# HVIBDC.net
KiCad netlist of a schematic drawn in EAGLE
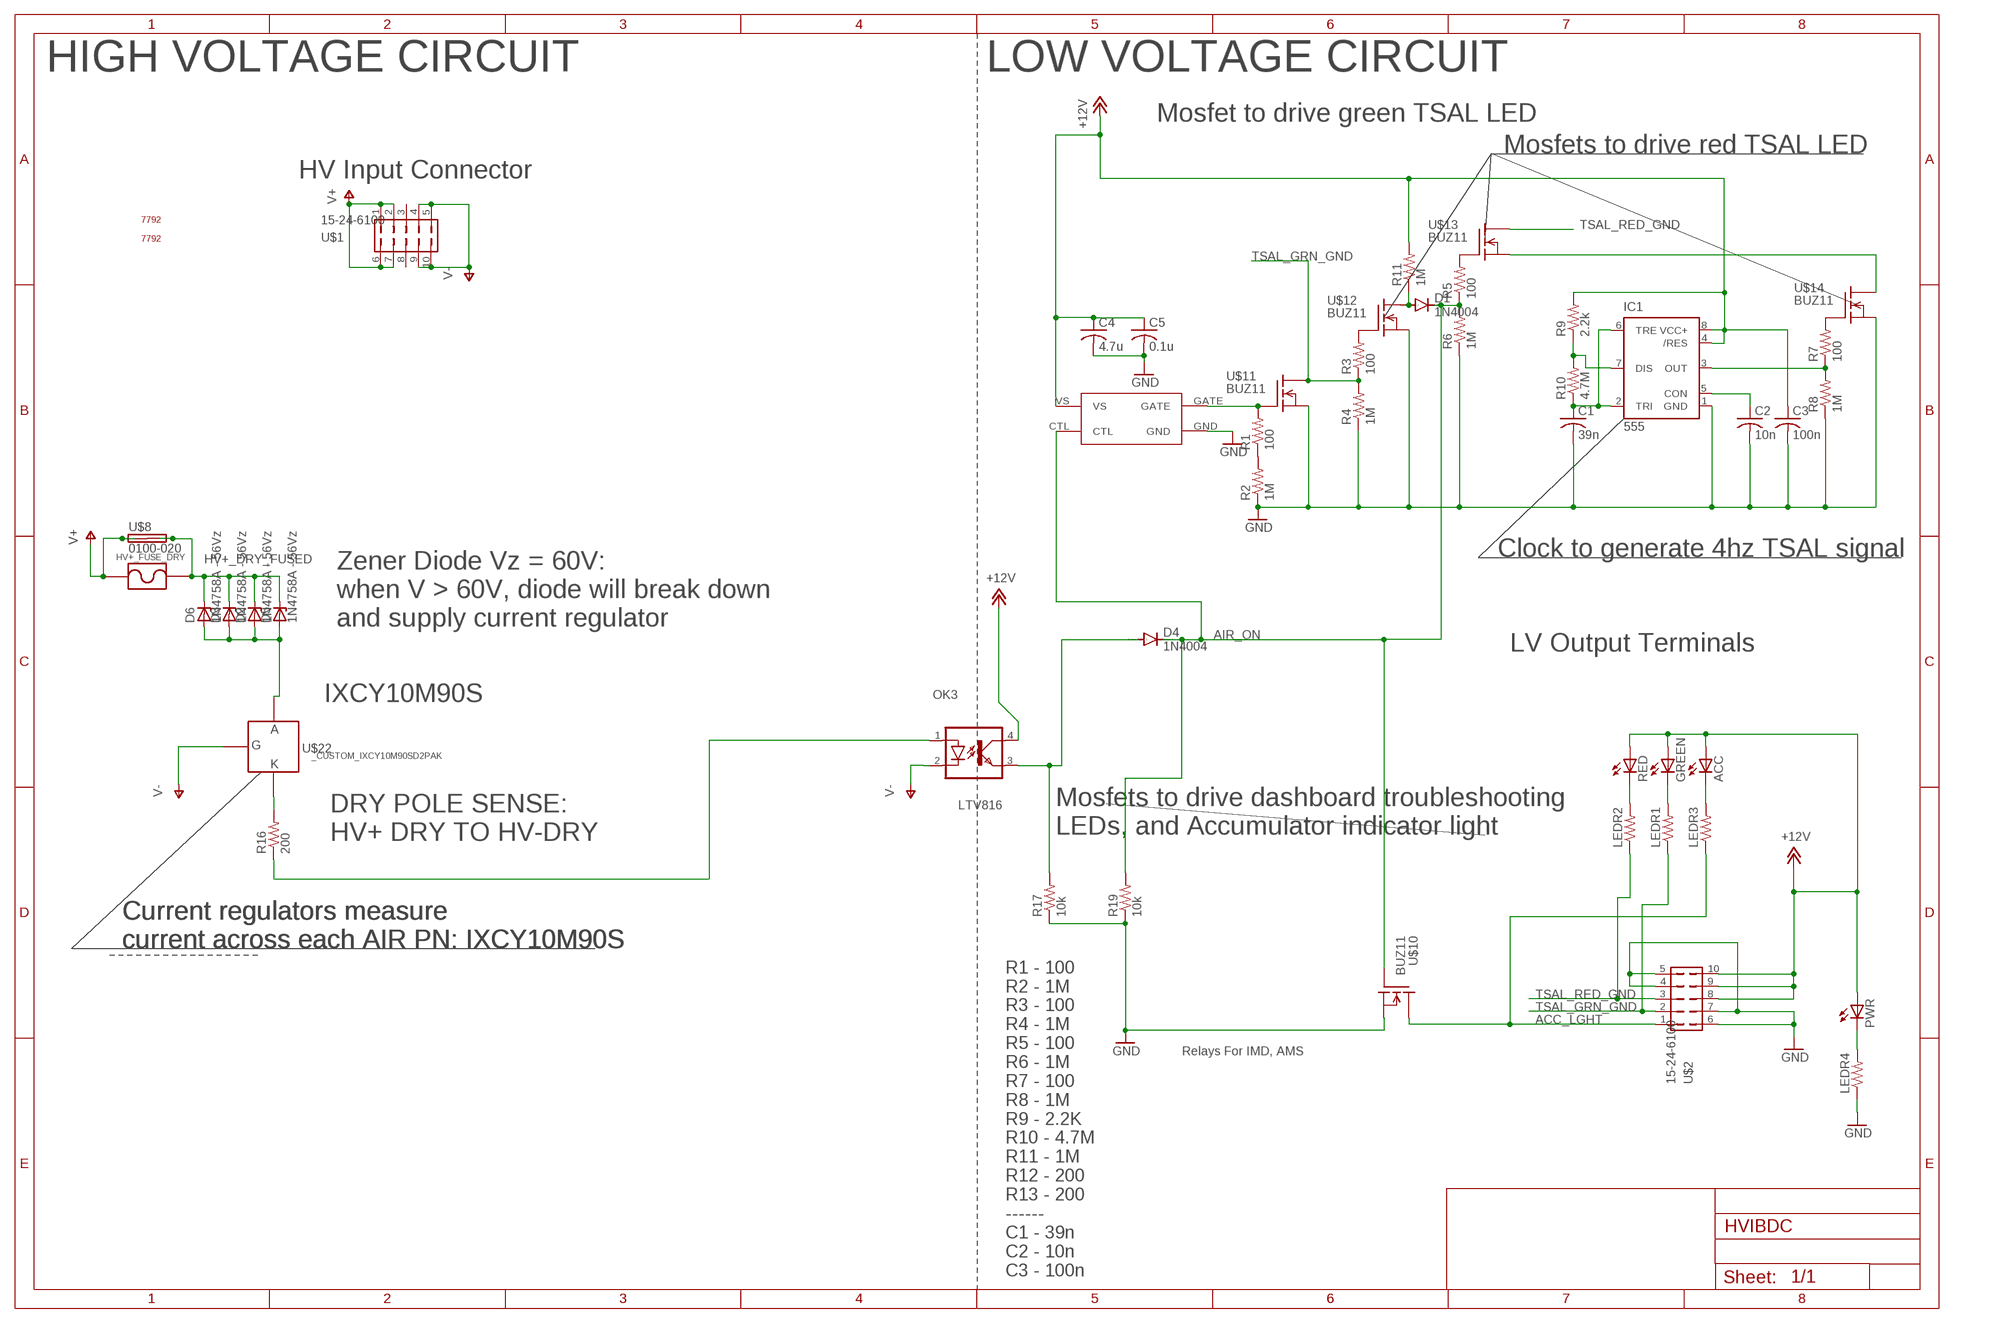
[diagram p0: schematic, sheet 1]

(export (version "E")
  (design (tool "Eeschema 10.0.6"))
  (components
    (comp (ref "ACC")
      (value "LEDCHIPLED_0805")
      (footprint "eagle-import:CHIPLED_0805")
      (libsource (lib "eagle-import") (part "LEDCHIPLED_0805"))
    )
    (comp (ref "C1")
      (value "39n")
      (footprint "eagle-import:C0805")
      (libsource (lib "eagle-import") (part "C-USC0805"))
    )
    (comp (ref "C2")
      (value "10n")
      (footprint "eagle-import:C0805")
      (libsource (lib "eagle-import") (part "C-USC0805"))
    )
    (comp (ref "C3")
      (value "100n")
      (footprint "eagle-import:C0805")
      (libsource (lib "eagle-import") (part "C-USC0805"))
    )
    (comp (ref "C4")
      (value "4.7u")
      (footprint "eagle-import:C0805")
      (libsource (lib "eagle-import") (part "C-USC0805"))
    )
    (comp (ref "C5")
      (value "0.1u")
      (footprint "eagle-import:C0805")
      (libsource (lib "eagle-import") (part "C-USC0805"))
    )
    (comp (ref "D1")
      (value "1N4004")
      (footprint "eagle-import:DO41-10")
      (libsource (lib "eagle-import") (part "1N4004"))
    )
    (comp (ref "D2")
      (value "1N4758A - 56Vz")
      (footprint "eagle-import:ZDIO12.5")
      (libsource (lib "eagle-import") (part "ZENER-DIODEZD-12.5"))
    )
    (comp (ref "D3")
      (value "1N4758A - 56Vz")
      (footprint "eagle-import:ZDIO12.5")
      (libsource (lib "eagle-import") (part "ZENER-DIODEZD-12.5"))
    )
    (comp (ref "D4")
      (value "1N4004")
      (footprint "eagle-import:DO41-10")
      (libsource (lib "eagle-import") (part "1N4004"))
    )
    (comp (ref "D5")
      (value "1N4758A - 56Vz")
      (footprint "eagle-import:ZDIO12.5")
      (libsource (lib "eagle-import") (part "ZENER-DIODEZD-12.5"))
    )
    (comp (ref "D6")
      (value "1N4758A - 56Vz")
      (footprint "eagle-import:ZDIO12.5")
      (libsource (lib "eagle-import") (part "ZENER-DIODEZD-12.5"))
    )
    (comp (ref "GREEN")
      (value "LEDCHIPLED_0805")
      (footprint "eagle-import:CHIPLED_0805")
      (libsource (lib "eagle-import") (part "LEDCHIPLED_0805"))
    )
    (comp (ref "HV+_FUSE_DRY")
      (value "_CUSTOM_PARTS_LF_885")
      (footprint "eagle-import:_CUSTOM_PARTS_LF_885")
      (libsource (lib "eagle-import") (part "_CUSTOM_PARTS_LF_885"))
    )
    (comp (ref "IC1")
      (value "555")
      (footprint "eagle-import:DIP08")
      (libsource (lib "eagle-import") (part "555P"))
    )
    (comp (ref "LEDR1")
      (value "R-US_R0805")
      (footprint "eagle-import:R0805")
      (libsource (lib "eagle-import") (part "R-US_R0805"))
    )
    (comp (ref "LEDR2")
      (value "R-US_R0805")
      (footprint "eagle-import:R0805")
      (libsource (lib "eagle-import") (part "R-US_R0805"))
    )
    (comp (ref "LEDR3")
      (value "R-US_R0805")
      (footprint "eagle-import:R0805")
      (libsource (lib "eagle-import") (part "R-US_R0805"))
    )
    (comp (ref "LEDR4")
      (value "R-US_R0805")
      (footprint "eagle-import:R0805")
      (libsource (lib "eagle-import") (part "R-US_R0805"))
    )
    (comp (ref "OK3")
      (value "LTV816")
      (footprint "eagle-import:DIL04")
      (libsource (lib "eagle-import") (part "LTV816"))
    )
    (comp (ref "PWR")
      (value "LEDCHIPLED_0805")
      (footprint "eagle-import:CHIPLED_0805")
      (libsource (lib "eagle-import") (part "LEDCHIPLED_0805"))
    )
    (comp (ref "R1")
      (value "100")
      (footprint "eagle-import:R0805")
      (libsource (lib "eagle-import") (part "resistor_348_R-US_R0805"))
    )
    (comp (ref "R2")
      (value "1M")
      (footprint "eagle-import:R0805")
      (libsource (lib "eagle-import") (part "resistor_348_R-US_R0805"))
    )
    (comp (ref "R3")
      (value "100")
      (footprint "eagle-import:R0805")
      (libsource (lib "eagle-import") (part "resistor_348_R-US_R0805"))
    )
    (comp (ref "R4")
      (value "1M")
      (footprint "eagle-import:R0805")
      (libsource (lib "eagle-import") (part "resistor_348_R-US_R0805"))
    )
    (comp (ref "R5")
      (value "100")
      (footprint "eagle-import:R0805")
      (libsource (lib "eagle-import") (part "resistor_348_R-US_R0805"))
    )
    (comp (ref "R6")
      (value "1M")
      (footprint "eagle-import:R0805")
      (libsource (lib "eagle-import") (part "resistor_348_R-US_R0805"))
    )
    (comp (ref "R7")
      (value "100")
      (footprint "eagle-import:R0805")
      (libsource (lib "eagle-import") (part "resistor_348_R-US_R0805"))
    )
    (comp (ref "R8")
      (value "1M")
      (footprint "eagle-import:R0805")
      (libsource (lib "eagle-import") (part "resistor_348_R-US_R0805"))
    )
    (comp (ref "R9")
      (value "2.2k")
      (footprint "eagle-import:R0805")
      (libsource (lib "eagle-import") (part "resistor_348_R-US_R0805"))
    )
    (comp (ref "R10")
      (value "4.7M")
      (footprint "eagle-import:R0805")
      (libsource (lib "eagle-import") (part "resistor_348_R-US_R0805"))
    )
    (comp (ref "R11")
      (value "1M")
      (footprint "eagle-import:R0805")
      (libsource (lib "eagle-import") (part "resistor_348_R-US_R0805"))
    )
    (comp (ref "R16")
      (value "200")
      (footprint "eagle-import:R2010")
      (libsource (lib "eagle-import") (part "Main_14107900_R-US_R2010"))
    )
    (comp (ref "R17")
      (value "10k")
      (footprint "eagle-import:R0805")
      (libsource (lib "eagle-import") (part "resistor_348_R-US_R0805"))
    )
    (comp (ref "R19")
      (value "10k")
      (footprint "eagle-import:R0805")
      (libsource (lib "eagle-import") (part "resistor_348_R-US_R0805"))
    )
    (comp (ref "RED")
      (value "LEDCHIPLED_0805")
      (footprint "eagle-import:CHIPLED_0805")
      (libsource (lib "eagle-import") (part "LEDCHIPLED_0805"))
    )
    (comp (ref "U$1")
      (value "15-24-6100")
      (footprint "eagle-import:15-24-6100")
      (libsource (lib "eagle-import") (part "15-24-6100"))
    )
    (comp (ref "U$2")
      (value "15-24-6100")
      (footprint "eagle-import:15-24-6100")
      (libsource (lib "eagle-import") (part "15-24-6100"))
    )
    (comp (ref "U$3")
      (value "7792")
      (footprint "eagle-import:7792")
      (libsource (lib "eagle-import") (part "7792"))
    )
    (comp (ref "U$4")
      (value "7792")
      (footprint "eagle-import:7792")
      (libsource (lib "eagle-import") (part "7792"))
    )
    (comp (ref "U$8")
      (value "0100-020")
      (footprint "eagle-import:0100-020")
      (libsource (lib "eagle-import") (part "0100-020"))
    )
    (comp (ref "U$10")
      (value "BUZ11")
      (footprint "eagle-import:TO220")
      (libsource (lib "eagle-import") (part "BUZ11"))
    )
    (comp (ref "U$11")
      (value "BUZ11")
      (footprint "eagle-import:TO220")
      (libsource (lib "eagle-import") (part "BUZ11"))
    )
    (comp (ref "U$12")
      (value "BUZ11")
      (footprint "eagle-import:TO220")
      (libsource (lib "eagle-import") (part "BUZ11"))
    )
    (comp (ref "U$13")
      (value "BUZ11")
      (footprint "eagle-import:TO220")
      (libsource (lib "eagle-import") (part "BUZ11"))
    )
    (comp (ref "U$14")
      (value "BUZ11")
      (footprint "eagle-import:TO220")
      (libsource (lib "eagle-import") (part "BUZ11"))
    )
    (comp (ref "U$15")
      (value "MIC4417")
      (footprint "eagle-import:PDM_2019_REVB_MIC4416YM4-TR")
      (libsource (lib "eagle-import") (part "MIC4417"))
    )
    (comp (ref "U$22")
      (value "_CUSTOM_IXCY10M90SD2PAK")
      (footprint "eagle-import:TO228P991X238-3")
      (libsource (lib "eagle-import") (part "_CUSTOM_IXCY10M90SD2PAK"))
    )
  )
  (nets
    (net (code "1") (name "+12V") (class "Default")
      (node (ref "ACC") (pin "A") (pinfunction "A_A") (pintype "passive"))
      (node (ref "C3") (pin "1") (pinfunction "1_1") (pintype "passive"))
      (node (ref "C4") (pin "1") (pinfunction "1_1") (pintype "passive"))
      (node (ref "C5") (pin "1") (pinfunction "1_1") (pintype "passive"))
      (node (ref "GREEN") (pin "A") (pinfunction "A_A") (pintype "passive"))
      (node (ref "IC1") (pin "4") (pinfunction "/RES_4") (pintype "input"))
      (node (ref "IC1") (pin "8") (pinfunction "VCC+_8") (pintype "power_in"))
      (node (ref "OK3") (pin "4") (pinfunction "COL_4") (pintype "passive"))
      (node (ref "PWR") (pin "A") (pinfunction "A_A") (pintype "passive"))
      (node (ref "R11") (pin "2") (pinfunction "2_2") (pintype "passive"))
      (node (ref "R9") (pin "2") (pinfunction "2_2") (pintype "passive"))
      (node (ref "RED") (pin "A") (pinfunction "A_A") (pintype "passive"))
      (node (ref "U$15") (pin "VS") (pinfunction "VS_VS") (pintype "bidirectional"))
      (node (ref "U$2") (pin "10") (pinfunction "10_10") (pintype "passive"))
      (node (ref "U$2") (pin "8") (pinfunction "8_8") (pintype "passive"))
      (node (ref "U$2") (pin "9") (pinfunction "9_9") (pintype "passive"))
    )
    (net (code "2") (name "/ACC_LGHT") (class "Default")
      (node (ref "LEDR3") (pin "1") (pinfunction "1_1") (pintype "passive"))
      (node (ref "U$10") (pin "2") (pinfunction "D_2") (pintype "passive"))
      (node (ref "U$2") (pin "1") (pinfunction "1_1") (pintype "passive"))
    )
    (net (code "3") (name "/AIR_ON") (class "Default")
      (node (ref "D1") (pin "C") (pinfunction "C_C") (pintype "passive"))
      (node (ref "D4") (pin "C") (pinfunction "C_C") (pintype "passive"))
      (node (ref "R19") (pin "2") (pinfunction "2_2") (pintype "passive"))
      (node (ref "R5") (pin "1") (pinfunction "1_1") (pintype "passive"))
      (node (ref "R6") (pin "2") (pinfunction "2_2") (pintype "passive"))
      (node (ref "U$10") (pin "1") (pinfunction "G_1") (pintype "passive"))
      (node (ref "U$15") (pin "CTL") (pinfunction "CTL_CTL") (pintype "bidirectional"))
    )
    (net (code "4") (name "/HV+_DRY_FUSED") (class "Default")
      (node (ref "D2") (pin "C") (pinfunction "C_C") (pintype "passive"))
      (node (ref "D3") (pin "C") (pinfunction "C_C") (pintype "passive"))
      (node (ref "D5") (pin "C") (pinfunction "C_C") (pintype "passive"))
      (node (ref "D6") (pin "C") (pinfunction "C_C") (pintype "passive"))
      (node (ref "HV+_FUSE_DRY") (pin "P$1") (pinfunction "P$1_P$1") (pintype "bidirectional"))
      (node (ref "U$8") (pin "P$2") (pinfunction "2A_P$2") (pintype "passive"))
      (node (ref "U$8") (pin "P$4") (pinfunction "2B_P$4") (pintype "passive"))
    )
    (net (code "5") (name "/TSAL_GRN_GND") (class "Default")
      (node (ref "LEDR1") (pin "1") (pinfunction "1_1") (pintype "passive"))
      (node (ref "R3") (pin "1") (pinfunction "1_1") (pintype "passive"))
      (node (ref "R4") (pin "2") (pinfunction "2_2") (pintype "passive"))
      (node (ref "U$11") (pin "2") (pinfunction "D_2") (pintype "passive"))
      (node (ref "U$2") (pin "2") (pinfunction "2_2") (pintype "passive"))
    )
    (net (code "6") (name "/TSAL_RED_GND") (class "Default")
      (node (ref "LEDR2") (pin "1") (pinfunction "1_1") (pintype "passive"))
      (node (ref "U$13") (pin "2") (pinfunction "D_2") (pintype "passive"))
      (node (ref "U$2") (pin "3") (pinfunction "3_3") (pintype "passive"))
    )
    (net (code "7") (name "GND") (class "Default")
      (node (ref "C1") (pin "2") (pinfunction "2_2") (pintype "passive"))
      (node (ref "C2") (pin "2") (pinfunction "2_2") (pintype "passive"))
      (node (ref "C3") (pin "2") (pinfunction "2_2") (pintype "passive"))
      (node (ref "C4") (pin "2") (pinfunction "2_2") (pintype "passive"))
      (node (ref "C5") (pin "2") (pinfunction "2_2") (pintype "passive"))
      (node (ref "IC1") (pin "1") (pinfunction "GND_1") (pintype "power_in"))
      (node (ref "LEDR4") (pin "1") (pinfunction "1_1") (pintype "passive"))
      (node (ref "R17") (pin "1") (pinfunction "1_1") (pintype "passive"))
      (node (ref "R19") (pin "1") (pinfunction "1_1") (pintype "passive"))
      (node (ref "R2") (pin "1") (pinfunction "1_1") (pintype "passive"))
      (node (ref "R4") (pin "1") (pinfunction "1_1") (pintype "passive"))
      (node (ref "R6") (pin "1") (pinfunction "1_1") (pintype "passive"))
      (node (ref "R8") (pin "1") (pinfunction "1_1") (pintype "passive"))
      (node (ref "U$10") (pin "3") (pinfunction "S_3") (pintype "passive"))
      (node (ref "U$11") (pin "3") (pinfunction "S_3") (pintype "passive"))
      (node (ref "U$12") (pin "3") (pinfunction "S_3") (pintype "passive"))
      (node (ref "U$14") (pin "3") (pinfunction "S_3") (pintype "passive"))
      (node (ref "U$15") (pin "GND") (pinfunction "GND_GND") (pintype "bidirectional"))
      (node (ref "U$2") (pin "4") (pinfunction "4_4") (pintype "passive"))
      (node (ref "U$2") (pin "5") (pinfunction "5_5") (pintype "passive"))
      (node (ref "U$2") (pin "6") (pinfunction "6_6") (pintype "passive"))
      (node (ref "U$2") (pin "7") (pinfunction "7_7") (pintype "passive"))
    )
    (net (code "8") (name "Net-(ACC-PadC)") (class "Default")
      (node (ref "ACC") (pin "C") (pinfunction "C_C") (pintype "passive"))
      (node (ref "LEDR3") (pin "2") (pinfunction "2_2") (pintype "passive"))
    )
    (net (code "9") (name "Net-(GREEN-PadC)") (class "Default")
      (node (ref "GREEN") (pin "C") (pinfunction "C_C") (pintype "passive"))
      (node (ref "LEDR1") (pin "2") (pinfunction "2_2") (pintype "passive"))
    )
    (net (code "10") (name "Net-(IC1-CON)") (class "Default")
      (node (ref "C2") (pin "1") (pinfunction "1_1") (pintype "passive"))
      (node (ref "IC1") (pin "5") (pinfunction "CON_5") (pintype "input"))
    )
    (net (code "11") (name "Net-(IC1-DIS)") (class "Default")
      (node (ref "IC1") (pin "7") (pinfunction "DIS_7") (pintype "input"))
      (node (ref "R10") (pin "2") (pinfunction "2_2") (pintype "passive"))
      (node (ref "R9") (pin "1") (pinfunction "1_1") (pintype "passive"))
    )
    (net (code "12") (name "Net-(IC1-OUT)") (class "Default")
      (node (ref "IC1") (pin "3") (pinfunction "OUT_3") (pintype "output"))
      (node (ref "R7") (pin "1") (pinfunction "1_1") (pintype "passive"))
      (node (ref "R8") (pin "2") (pinfunction "2_2") (pintype "passive"))
    )
    (net (code "13") (name "Net-(IC1-TRE)") (class "Default")
      (node (ref "C1") (pin "1") (pinfunction "1_1") (pintype "passive"))
      (node (ref "IC1") (pin "2") (pinfunction "TRI_2") (pintype "input"))
      (node (ref "IC1") (pin "6") (pinfunction "TRE_6") (pintype "input"))
      (node (ref "R10") (pin "1") (pinfunction "1_1") (pintype "passive"))
    )
    (net (code "14") (name "Net-(LEDR2-Pad2)") (class "Default")
      (node (ref "LEDR2") (pin "2") (pinfunction "2_2") (pintype "passive"))
      (node (ref "RED") (pin "C") (pinfunction "C_C") (pintype "passive"))
    )
    (net (code "15") (name "Net-(LEDR4-Pad2)") (class "Default")
      (node (ref "LEDR4") (pin "2") (pinfunction "2_2") (pintype "passive"))
      (node (ref "PWR") (pin "C") (pinfunction "C_C") (pintype "passive"))
    )
    (net (code "16") (name "Net-(OK3-A)") (class "Default")
      (node (ref "OK3") (pin "1") (pinfunction "A_1") (pintype "passive"))
      (node (ref "R16") (pin "1") (pinfunction "1_1") (pintype "passive"))
    )
    (net (code "17") (name "Net-(OK3-EMIT)") (class "Default")
      (node (ref "D4") (pin "A") (pinfunction "A_A") (pintype "passive"))
      (node (ref "OK3") (pin "3") (pinfunction "EMIT_3") (pintype "passive"))
      (node (ref "R17") (pin "2") (pinfunction "2_2") (pintype "passive"))
    )
    (net (code "18") (name "Net-(R1-Pad1)") (class "Default")
      (node (ref "R1") (pin "1") (pinfunction "1_1") (pintype "passive"))
      (node (ref "R2") (pin "2") (pinfunction "2_2") (pintype "passive"))
    )
    (net (code "19") (name "Net-(U$11-G)") (class "Default")
      (node (ref "R1") (pin "2") (pinfunction "2_2") (pintype "passive"))
      (node (ref "U$11") (pin "1") (pinfunction "G_1") (pintype "passive"))
      (node (ref "U$15") (pin "GATE") (pinfunction "GATE_GATE") (pintype "bidirectional"))
    )
    (net (code "20") (name "Net-(U$12-D)") (class "Default")
      (node (ref "D1") (pin "A") (pinfunction "A_A") (pintype "passive"))
      (node (ref "R11") (pin "1") (pinfunction "1_1") (pintype "passive"))
      (node (ref "U$12") (pin "2") (pinfunction "D_2") (pintype "passive"))
    )
    (net (code "21") (name "Net-(U$12-G)") (class "Default")
      (node (ref "R3") (pin "2") (pinfunction "2_2") (pintype "passive"))
      (node (ref "U$12") (pin "1") (pinfunction "G_1") (pintype "passive"))
    )
    (net (code "22") (name "Net-(U$13-G)") (class "Default")
      (node (ref "R5") (pin "2") (pinfunction "2_2") (pintype "passive"))
      (node (ref "U$13") (pin "1") (pinfunction "G_1") (pintype "passive"))
    )
    (net (code "23") (name "Net-(U$13-S)") (class "Default")
      (node (ref "U$13") (pin "3") (pinfunction "S_3") (pintype "passive"))
      (node (ref "U$14") (pin "2") (pinfunction "D_2") (pintype "passive"))
    )
    (net (code "24") (name "Net-(U$14-G)") (class "Default")
      (node (ref "R7") (pin "2") (pinfunction "2_2") (pintype "passive"))
      (node (ref "U$14") (pin "1") (pinfunction "G_1") (pintype "passive"))
    )
    (net (code "25") (name "Net-(U$22-A)") (class "Default")
      (node (ref "D2") (pin "A") (pinfunction "A_A") (pintype "passive"))
      (node (ref "D3") (pin "A") (pinfunction "A_A") (pintype "passive"))
      (node (ref "D5") (pin "A") (pinfunction "A_A") (pintype "passive"))
      (node (ref "D6") (pin "A") (pinfunction "A_A") (pintype "passive"))
      (node (ref "U$22") (pin "3") (pinfunction "A_3") (pintype "bidirectional"))
    )
    (net (code "26") (name "Net-(U$22-K)") (class "Default")
      (node (ref "R16") (pin "2") (pinfunction "2_2") (pintype "passive"))
      (node (ref "U$22") (pin "2") (pinfunction "K_2") (pintype "bidirectional"))
    )
    (net (code "27") (name "V+") (class "Default")
      (node (ref "HV+_FUSE_DRY") (pin "P$2") (pinfunction "P$2_P$2") (pintype "bidirectional"))
      (node (ref "U$1") (pin "1") (pinfunction "1_1") (pintype "passive"))
      (node (ref "U$1") (pin "2") (pinfunction "2_2") (pintype "passive"))
      (node (ref "U$1") (pin "6") (pinfunction "6_6") (pintype "passive"))
      (node (ref "U$1") (pin "7") (pinfunction "7_7") (pintype "passive"))
      (node (ref "U$8") (pin "P$1") (pinfunction "1A_P$1") (pintype "passive"))
      (node (ref "U$8") (pin "P$3") (pinfunction "1B_P$3") (pintype "passive"))
    )
    (net (code "28") (name "V-") (class "Default")
      (node (ref "OK3") (pin "2") (pinfunction "C_2") (pintype "passive"))
      (node (ref "U$1") (pin "10") (pinfunction "10_10") (pintype "passive"))
      (node (ref "U$1") (pin "4") (pinfunction "4_4") (pintype "passive"))
      (node (ref "U$1") (pin "5") (pinfunction "5_5") (pintype "passive"))
      (node (ref "U$1") (pin "9") (pinfunction "9_9") (pintype "passive"))
      (node (ref "U$22") (pin "1") (pinfunction "G_1") (pintype "bidirectional"))
    )
    (net (code "29") (name "unconnected-(U$1-Pad3)") (class "Default")
      (node (ref "U$1") (pin "3") (pinfunction "3_3") (pintype "passive"))
    )
    (net (code "30") (name "unconnected-(U$1-Pad8)") (class "Default")
      (node (ref "U$1") (pin "8") (pinfunction "8_8") (pintype "passive"))
    )
  )
)
